# breadboardpower.net
KiCad netlist of a schematic drawn in EAGLE
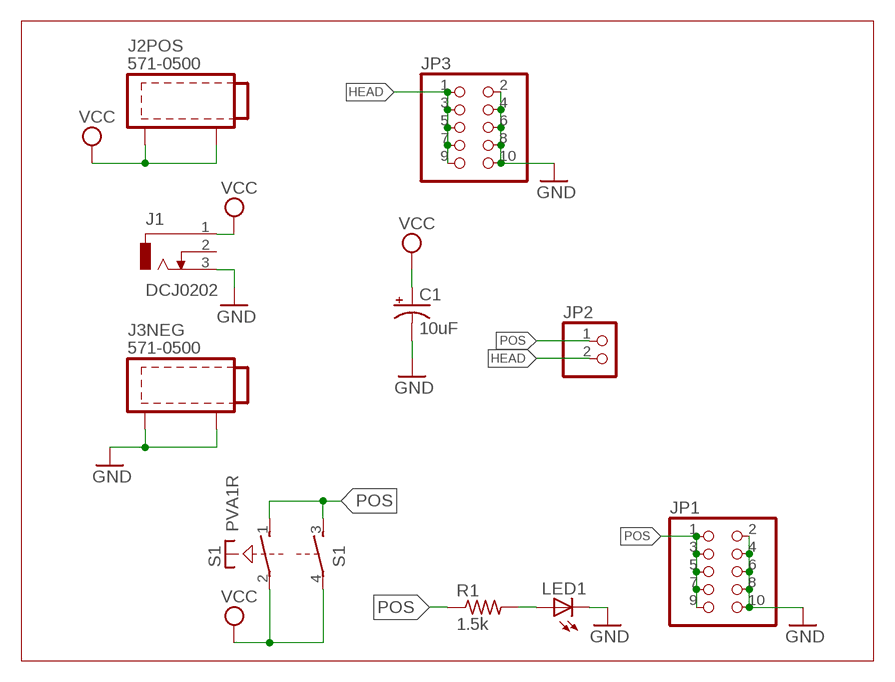
[diagram p0: schematic, sheet 1]

(export (version "E")
  (design (tool "Eeschema 10.0.6"))
  (components
    (comp (ref "C1")
      (value "10uF")
      (footprint "eagle-import:E2,5-5")
      (libsource (lib "eagle-import") (part "CPOL-USE2.5-5"))
    )
    (comp (ref "J1")
      (value "DCJ0202")
      (footprint "eagle-import:DCJ0202")
      (libsource (lib "eagle-import") (part "DCJ0202"))
    )
    (comp (ref "J2POS")
      (value "571-0500")
      (footprint "eagle-import:571-0500")
      (libsource (lib "eagle-import") (part "571-0500"))
    )
    (comp (ref "J3NEG")
      (value "571-0500")
      (footprint "eagle-import:571-0500")
      (libsource (lib "eagle-import") (part "571-0500"))
    )
    (comp (ref "JP1")
      (value "PINHD-2X5")
      (footprint "eagle-import:2X05")
      (libsource (lib "eagle-import") (part "PINHD-2X5"))
    )
    (comp (ref "JP2")
      (value "PINHD-1X2")
      (footprint "eagle-import:1X02")
      (libsource (lib "eagle-import") (part "PINHD-1X2"))
    )
    (comp (ref "JP3")
      (value "PINHD-2X5")
      (footprint "eagle-import:2X05")
      (libsource (lib "eagle-import") (part "PINHD-2X5"))
    )
    (comp (ref "LED1")
      (value "LED3MM")
      (footprint "eagle-import:LED3MM")
      (libsource (lib "eagle-import") (part "LED3MM"))
    )
    (comp (ref "R1")
      (value "1.5k")
      (footprint "eagle-import:0207_10")
      (libsource (lib "eagle-import") (part "R-US_0207/10"))
    )
    (comp (ref "S1")
      (value "PVA1R")
      (footprint "eagle-import:PVA1R")
      (libsource (lib "eagle-import") (part "PVA1R"))
    )
  )
  (nets
    (net (code "1") (name "GND") (class "Default")
      (node (ref "C1") (pin "-") (pinfunction "-_-") (pintype "passive"))
      (node (ref "J1") (pin "3") (pinfunction "3_3") (pintype "passive"))
      (node (ref "J3NEG") (pin "1") (pinfunction "1_1") (pintype "passive"))
      (node (ref "J3NEG") (pin "2") (pinfunction "2_2") (pintype "passive"))
      (node (ref "JP1") (pin "10") (pinfunction "10_10") (pintype "passive"))
      (node (ref "JP1") (pin "2") (pinfunction "2_2") (pintype "passive"))
      (node (ref "JP1") (pin "4") (pinfunction "4_4") (pintype "passive"))
      (node (ref "JP1") (pin "6") (pinfunction "6_6") (pintype "passive"))
      (node (ref "JP1") (pin "8") (pinfunction "8_8") (pintype "passive"))
      (node (ref "JP3") (pin "10") (pinfunction "10_10") (pintype "passive"))
      (node (ref "JP3") (pin "2") (pinfunction "2_2") (pintype "passive"))
      (node (ref "JP3") (pin "4") (pinfunction "4_4") (pintype "passive"))
      (node (ref "JP3") (pin "6") (pinfunction "6_6") (pintype "passive"))
      (node (ref "JP3") (pin "8") (pinfunction "8_8") (pintype "passive"))
      (node (ref "LED1") (pin "K") (pinfunction "C_K") (pintype "passive"))
    )
    (net (code "2") (name "HEAD") (class "Default")
      (node (ref "JP2") (pin "2") (pinfunction "2_2") (pintype "passive"))
      (node (ref "JP3") (pin "1") (pinfunction "1_1") (pintype "passive"))
      (node (ref "JP3") (pin "3") (pinfunction "3_3") (pintype "passive"))
      (node (ref "JP3") (pin "5") (pinfunction "5_5") (pintype "passive"))
      (node (ref "JP3") (pin "7") (pinfunction "7_7") (pintype "passive"))
      (node (ref "JP3") (pin "9") (pinfunction "9_9") (pintype "passive"))
    )
    (net (code "3") (name "Net-(LED1-PadA)") (class "Default")
      (node (ref "LED1") (pin "A") (pinfunction "A_A") (pintype "passive"))
      (node (ref "R1") (pin "2") (pinfunction "2_2") (pintype "passive"))
    )
    (net (code "4") (name "POS") (class "Default")
      (node (ref "JP1") (pin "1") (pinfunction "1_1") (pintype "passive"))
      (node (ref "JP1") (pin "3") (pinfunction "3_3") (pintype "passive"))
      (node (ref "JP1") (pin "5") (pinfunction "5_5") (pintype "passive"))
      (node (ref "JP1") (pin "7") (pinfunction "7_7") (pintype "passive"))
      (node (ref "JP1") (pin "9") (pinfunction "9_9") (pintype "passive"))
      (node (ref "JP2") (pin "1") (pinfunction "1_1") (pintype "passive"))
      (node (ref "R1") (pin "1") (pinfunction "1_1") (pintype "passive"))
      (node (ref "S1") (pin "1") (pinfunction "S_1") (pintype "passive"))
      (node (ref "S1") (pin "3") (pinfunction "S_3") (pintype "passive"))
    )
    (net (code "5") (name "VCC") (class "Default")
      (node (ref "C1") (pin "+") (pinfunction "+_+") (pintype "passive"))
      (node (ref "J1") (pin "1") (pinfunction "1_1") (pintype "passive"))
      (node (ref "J2POS") (pin "1") (pinfunction "1_1") (pintype "passive"))
      (node (ref "J2POS") (pin "2") (pinfunction "2_2") (pintype "passive"))
      (node (ref "S1") (pin "2") (pinfunction "P_2") (pintype "passive"))
      (node (ref "S1") (pin "4") (pinfunction "P_4") (pintype "passive"))
    )
    (net (code "6") (name "unconnected-(J1-Pad2)") (class "Default")
      (node (ref "J1") (pin "2") (pinfunction "2_2") (pintype "passive"))
    )
  )
)
